# AD8318.net
KiCad netlist of a schematic drawn in Altium Designer
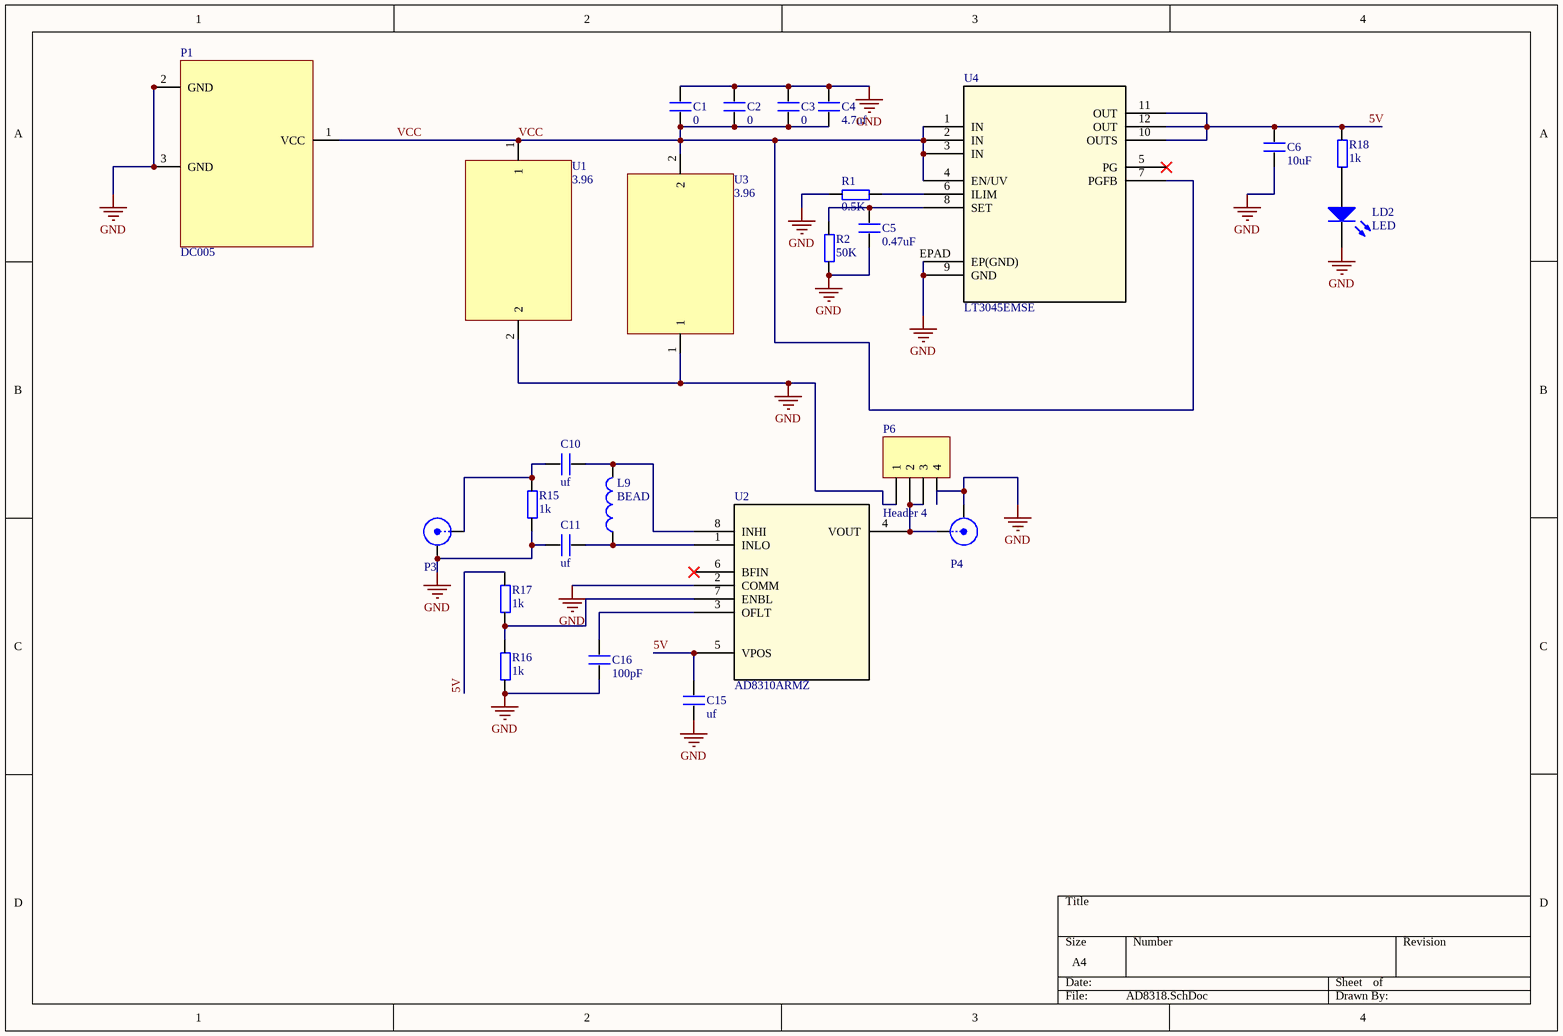
[diagram p0: AD8318.SchDoc]

(export (version "E")
  (design (tool "Eeschema 10.0.6"))
  (components
    (comp (ref "C1")
      (value "0")
      (footprint "CAP 1.5*4*8")
      (description "Capacitor")
      (libsource (lib "MYLIB") (part "C"))
    )
    (comp (ref "C2")
      (value "0")
      (footprint "CAP 1.5*4*8")
      (description "Capacitor")
      (libsource (lib "MYLIB") (part "C"))
    )
    (comp (ref "C3")
      (value "0")
      (footprint "0603C")
      (description "Capacitor")
      (libsource (lib "MYLIB") (part "C"))
    )
    (comp (ref "C4")
      (value "4.7uf")
      (footprint "0603C")
      (description "Capacitor")
      (libsource (lib "MYLIB") (part "C"))
    )
    (comp (ref "C5")
      (value "0.47uF")
      (footprint "0402")
      (description "Capacitor")
      (libsource (lib "MYLIB") (part "C"))
    )
    (comp (ref "C6")
      (value "10uF")
      (footprint "0402")
      (description "Capacitor")
      (libsource (lib "MYLIB") (part "C"))
    )
    (comp (ref "C10")
      (value "uf")
      (footprint "0603C")
      (description "Capacitor")
      (libsource (lib "MYLIB") (part "C"))
    )
    (comp (ref "C11")
      (value "uf")
      (footprint "0603C")
      (description "Capacitor")
      (libsource (lib "MYLIB") (part "C"))
    )
    (comp (ref "C15")
      (value "uf")
      (footprint "0603C")
      (description "Capacitor")
      (libsource (lib "MYLIB") (part "C"))
    )
    (comp (ref "C16")
      (value "100pF")
      (footprint "0603C")
      (description "Capacitor")
      (libsource (lib "MYLIB") (part "C"))
    )
    (comp (ref "L9")
      (value "BEAD")
      (footprint "0603L")
      (description "Inductor")
      (fields (field (name "PUBLISHER") "Altium Limited"))
      (libsource (lib "MYLIB") (part "Inductor"))
    )
    (comp (ref "LD2")
      (value "LED")
      (footprint "SMDLED")
      (description "Typical RED, GREEN, YELLOW, AMBER GaAs LED")
      (fields (field (name "PUBLISHER") "Altium Limited"))
      (libsource (lib "MYLIB") (part "LED"))
    )
    (comp (ref "P1") (value "DC005") (footprint "DC10B") (libsource (lib "MYLIB") (part "DC005")))
    (comp (ref "P3")
      (value "SMA")
      (footprint "SMA")
      (description "SMA Connector")
      (libsource (lib "MYLIB") (part "SMA"))
    )
    (comp (ref "P4")
      (value "SMA")
      (footprint "SMA")
      (description "SMA Connector")
      (libsource (lib "MYLIB") (part "SMA"))
    )
    (comp (ref "P6")
      (value "Header 4")
      (footprint "HDR1X4")
      (description "Header, 4-Pin")
      (fields (field (name "PUBLISHER") "Altium Limited"))
      (libsource (lib "MYLIB") (part "Header 4"))
    )
    (comp (ref "R1")
      (value "0.5K")
      (footprint "0402")
      (description "Resistor")
      (libsource (lib "MYLIB") (part "Resistor"))
    )
    (comp (ref "R2")
      (value "50K")
      (footprint "0402")
      (description "Resistor")
      (libsource (lib "MYLIB") (part "Resistor"))
    )
    (comp (ref "R15")
      (value "1k")
      (footprint "0603R")
      (description "Resistor")
      (libsource (lib "MYLIB") (part "Resistor"))
    )
    (comp (ref "R16")
      (value "1k")
      (footprint "0402")
      (description "Resistor")
      (libsource (lib "MYLIB") (part "Resistor"))
    )
    (comp (ref "R17")
      (value "1k")
      (footprint "0402")
      (description "Resistor")
      (libsource (lib "MYLIB") (part "Resistor"))
    )
    (comp (ref "R18")
      (value "1k")
      (footprint "0603R")
      (description "Resistor")
      (libsource (lib "MYLIB") (part "Resistor"))
    )
    (comp (ref "U1") (value "3.96") (footprint "3.96") (libsource (lib "MYLIB") (part "3.96")))
    (comp (ref "U2")
      (value "AD8310ARMZ")
      (footprint "RM_8_ADI")
      (description "No Description Available")
      (fields (field (name "COPYRIGHT") "Copyright (C) 2018 Accelerated Designs. All rights reserved"))
      (libsource (lib "MYLIB") (part "AD8310ARMZ"))
    )
    (comp (ref "U3") (value "3.96") (footprint "3.96") (libsource (lib "") (part "3.96_1")))
    (comp (ref "U4")
      (value "LT3045EMSE")
      (footprint "MSOP12-MSE-RevG_ADI")
      (description "No Description Available")
      (fields (field (name "COPYRIGHT") "Copyright (C) 2018 Accelerated Designs. All rights reserved"))
      (libsource (lib "MYLIB") (part "LT3045EMSE"))
    )
  )
  (nets
    (net (code "1") (name "/5V") (class "Default")
      (node (ref "C15") (pin "2") (pintype "passive"))
      (node (ref "C6") (pin "2") (pintype "passive"))
      (node (ref "R17") (pin "2") (pintype "passive"))
      (node (ref "R18") (pin "2") (pintype "passive"))
      (node (ref "U2") (pin "5") (pinfunction "VPOS_5") (pintype "power_in"))
      (node (ref "U4") (pin "10") (pinfunction "OUTS_10") (pintype "passive"))
      (node (ref "U4") (pin "11") (pinfunction "OUT_11") (pintype "passive"))
      (node (ref "U4") (pin "12") (pinfunction "OUT_12") (pintype "passive"))
    )
    (net (code "2") (name "/VCC") (class "Default")
      (node (ref "C1") (pin "1") (pintype "passive"))
      (node (ref "C2") (pin "1") (pintype "passive"))
      (node (ref "C3") (pin "1") (pintype "passive"))
      (node (ref "C4") (pin "1") (pintype "passive"))
      (node (ref "P1") (pin "1") (pinfunction "VCC_1") (pintype "passive"))
      (node (ref "U1") (pin "1") (pinfunction "1_1") (pintype "passive"))
      (node (ref "U3") (pin "2") (pinfunction "2_2") (pintype "passive"))
      (node (ref "U4") (pin "1") (pinfunction "IN_1") (pintype "passive"))
      (node (ref "U4") (pin "2") (pinfunction "IN_2") (pintype "passive"))
      (node (ref "U4") (pin "3") (pinfunction "IN_3") (pintype "passive"))
      (node (ref "U4") (pin "4") (pinfunction "EN/UV_4") (pintype "passive"))
      (node (ref "U4") (pin "7") (pinfunction "PGFB_7") (pintype "passive"))
    )
    (net (code "3") (name "GND") (class "Default")
      (node (ref "C1") (pin "2") (pintype "passive"))
      (node (ref "C11") (pin "1") (pintype "passive"))
      (node (ref "C15") (pin "1") (pintype "passive"))
      (node (ref "C16") (pin "1") (pintype "passive"))
      (node (ref "C2") (pin "2") (pintype "passive"))
      (node (ref "C3") (pin "2") (pintype "passive"))
      (node (ref "C4") (pin "2") (pintype "passive"))
      (node (ref "C5") (pin "2") (pintype "passive"))
      (node (ref "C6") (pin "1") (pintype "passive"))
      (node (ref "LD2") (pin "2") (pinfunction "K_2") (pintype "passive"))
      (node (ref "P1") (pin "2") (pinfunction "GND_2") (pintype "passive"))
      (node (ref "P1") (pin "3") (pinfunction "GND_3") (pintype "passive"))
      (node (ref "P3") (pin "2") (pinfunction "Y_2") (pintype "passive"))
      (node (ref "P4") (pin "2") (pinfunction "Y_2") (pintype "passive"))
      (node (ref "P6") (pin "1") (pinfunction "1_1") (pintype "passive"))
      (node (ref "P6") (pin "4") (pinfunction "4_4") (pintype "passive"))
      (node (ref "R1") (pin "1") (pintype "passive"))
      (node (ref "R15") (pin "1") (pintype "passive"))
      (node (ref "R16") (pin "1") (pintype "passive"))
      (node (ref "R2") (pin "1") (pintype "passive"))
      (node (ref "U1") (pin "2") (pinfunction "2_2") (pintype "passive"))
      (node (ref "U2") (pin "2") (pinfunction "COMM_2") (pintype "passive"))
      (node (ref "U3") (pin "1") (pinfunction "1_1") (pintype "passive"))
      (node (ref "U4") (pin "9") (pinfunction "GND_9") (pintype "passive"))
      (node (ref "U4") (pin "EPAD") (pinfunction "EP(GND)_EPAD") (pintype "passive"))
    )
    (net (code "4") (name "Net-(LD2-A)") (class "Default")
      (node (ref "LD2") (pin "1") (pinfunction "A_1") (pintype "passive"))
      (node (ref "R18") (pin "1") (pintype "passive"))
    )
    (net (code "5") (name "Net-(P3-X)") (class "Default")
      (node (ref "C10") (pin "1") (pintype "passive"))
      (node (ref "P3") (pin "1") (pinfunction "X_1") (pintype "passive"))
      (node (ref "R15") (pin "2") (pintype "passive"))
    )
    (net (code "6") (name "Net-(P4-X)") (class "Default")
      (node (ref "P4") (pin "1") (pinfunction "X_1") (pintype "passive"))
      (node (ref "P6") (pin "2") (pinfunction "2_2") (pintype "passive"))
      (node (ref "P6") (pin "3") (pinfunction "3_3") (pintype "passive"))
      (node (ref "U2") (pin "4") (pinfunction "VOUT_4") (pintype "passive"))
    )
    (net (code "7") (name "Net-(U2-ENBL)") (class "Default")
      (node (ref "R16") (pin "2") (pintype "passive"))
      (node (ref "R17") (pin "1") (pintype "passive"))
      (node (ref "U2") (pin "7") (pinfunction "ENBL_7") (pintype "passive"))
    )
    (net (code "8") (name "Net-(U2-INHI)") (class "Default")
      (node (ref "C10") (pin "2") (pintype "passive"))
      (node (ref "L9") (pin "2") (pinfunction "2_2") (pintype "passive"))
      (node (ref "U2") (pin "8") (pinfunction "INHI_8") (pintype "passive"))
    )
    (net (code "9") (name "Net-(U2-INLO)") (class "Default")
      (node (ref "C11") (pin "2") (pintype "passive"))
      (node (ref "L9") (pin "1") (pinfunction "1_1") (pintype "passive"))
      (node (ref "U2") (pin "1") (pinfunction "INLO_1") (pintype "passive"))
    )
    (net (code "10") (name "Net-(U2-OFLT)") (class "Default")
      (node (ref "C16") (pin "2") (pintype "passive"))
      (node (ref "U2") (pin "3") (pinfunction "OFLT_3") (pintype "passive"))
    )
    (net (code "11") (name "Net-(U4-ILIM)") (class "Default")
      (node (ref "R1") (pin "2") (pintype "passive"))
      (node (ref "U4") (pin "6") (pinfunction "ILIM_6") (pintype "passive"))
    )
    (net (code "12") (name "Net-(U4-SET)") (class "Default")
      (node (ref "C5") (pin "1") (pintype "passive"))
      (node (ref "R2") (pin "2") (pintype "passive"))
      (node (ref "U4") (pin "8") (pinfunction "SET_8") (pintype "passive"))
    )
    (net (code "13") (name "unconnected-(U2-BFIN-Pad6)") (class "Default")
      (node (ref "U2") (pin "6") (pinfunction "BFIN_6") (pintype "passive+no_connect"))
    )
    (net (code "14") (name "unconnected-(U4-PG-Pad5)") (class "Default")
      (node (ref "U4") (pin "5") (pinfunction "PG_5") (pintype "passive+no_connect"))
    )
  )
)
